# Sheet3.net
KiCad netlist of a schematic drawn in Altium Designer
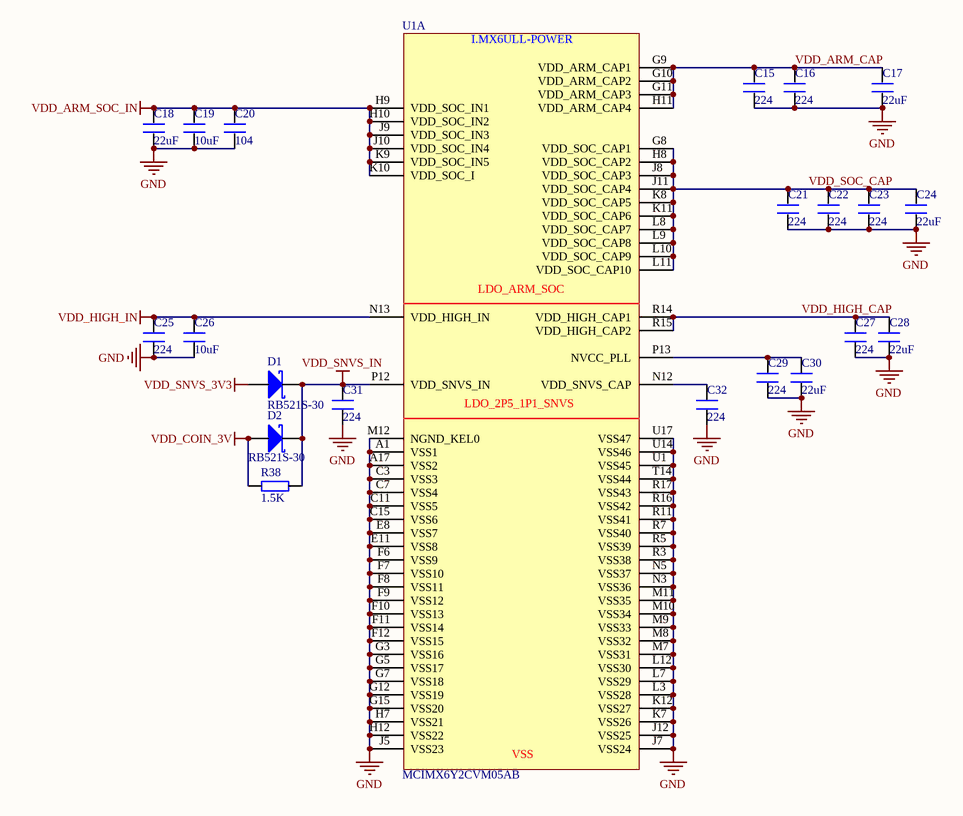
[diagram p0: Sheet3.SchDoc]

(export (version "E")
  (design (tool "Eeschema 10.0.6"))
  (components
    (comp (ref "C15")
      (value "224")
      (footprint "C 0402")
      (libsource (lib "IMX6ULL_CORE(核心板)_V1.4") (part "C"))
    )
    (comp (ref "C16")
      (value "224")
      (footprint "C 0402")
      (libsource (lib "IMX6ULL_CORE(核心板)_V1.4") (part "C"))
    )
    (comp (ref "C17")
      (value "22uF")
      (footprint "C 0402")
      (libsource (lib "IMX6ULL_CORE(核心板)_V1.4") (part "C"))
    )
    (comp (ref "C18")
      (value "22uF")
      (footprint "C 0402")
      (libsource (lib "IMX6ULL_CORE(核心板)_V1.4") (part "C"))
    )
    (comp (ref "C19")
      (value "10uF")
      (footprint "C 0402")
      (libsource (lib "IMX6ULL_CORE(核心板)_V1.4") (part "C"))
    )
    (comp (ref "C20")
      (value "104")
      (footprint "C 0402")
      (libsource (lib "IMX6ULL_CORE(核心板)_V1.4") (part "C"))
    )
    (comp (ref "C21")
      (value "224")
      (footprint "C 0402")
      (libsource (lib "IMX6ULL_CORE(核心板)_V1.4") (part "C"))
    )
    (comp (ref "C22")
      (value "224")
      (footprint "C 0402")
      (libsource (lib "IMX6ULL_CORE(核心板)_V1.4") (part "C"))
    )
    (comp (ref "C23")
      (value "224")
      (footprint "C 0402")
      (libsource (lib "IMX6ULL_CORE(核心板)_V1.4") (part "C"))
    )
    (comp (ref "C24")
      (value "22uF")
      (footprint "C 0402")
      (libsource (lib "IMX6ULL_CORE(核心板)_V1.4") (part "C"))
    )
    (comp (ref "C25")
      (value "224")
      (footprint "C 0402")
      (libsource (lib "IMX6ULL_CORE(核心板)_V1.4") (part "C"))
    )
    (comp (ref "C26")
      (value "10uF")
      (footprint "C 0402")
      (libsource (lib "IMX6ULL_CORE(核心板)_V1.4") (part "C"))
    )
    (comp (ref "C27")
      (value "224")
      (footprint "C 0402")
      (libsource (lib "IMX6ULL_CORE(核心板)_V1.4") (part "C"))
    )
    (comp (ref "C28")
      (value "22uF")
      (footprint "C 0402")
      (libsource (lib "IMX6ULL_CORE(核心板)_V1.4") (part "C"))
    )
    (comp (ref "C29")
      (value "224")
      (footprint "C 0402")
      (libsource (lib "IMX6ULL_CORE(核心板)_V1.4") (part "C"))
    )
    (comp (ref "C30")
      (value "22uF")
      (footprint "C 0402")
      (libsource (lib "IMX6ULL_CORE(核心板)_V1.4") (part "C"))
    )
    (comp (ref "C31")
      (value "224")
      (footprint "C 0402")
      (libsource (lib "IMX6ULL_CORE(核心板)_V1.4") (part "C"))
    )
    (comp (ref "C32")
      (value "224")
      (footprint "C 0402")
      (libsource (lib "IMX6ULL_CORE(核心板)_V1.4") (part "C"))
    )
    (comp (ref "D1")
      (value "RB521S-30")
      (footprint "SOD-523")
      (libsource (lib "IMX6ULL_CORE(核心板)_V1.4") (part "RB521S-30"))
    )
    (comp (ref "D2")
      (value "RB521S-30")
      (footprint "SOD-523")
      (libsource (lib "IMX6ULL_CORE(核心板)_V1.4") (part "RB521S-30"))
    )
    (comp (ref "R38")
      (value "1.5K")
      (footprint "R 0402")
      (libsource (lib "IMX6ULL_CORE(核心板)_V1.4") (part "R"))
    )
    (comp (ref "U1")
      (value "MCIMX6Y2CVM05AB")
      (footprint "BGA289C80P17X17_1400X1400X132")
      (libsource (lib "IMX6ULL_CORE(核心板)_V1.4") (part "MCIMX6Y2CVM05AB"))
    )
  )
  (nets
    (net (code "1") (name "/VDD_ARM_CAP") (class "Default")
      (node (ref "C15") (pin "2") (pintype "passive"))
      (node (ref "C16") (pin "2") (pintype "passive"))
      (node (ref "C17") (pin "2") (pintype "passive"))
      (node (ref "U1") (pin "G10") (pinfunction "VDD_ARM_CAP2_G10") (pintype "passive"))
      (node (ref "U1") (pin "G11") (pinfunction "VDD_ARM_CAP3_G11") (pintype "passive"))
      (node (ref "U1") (pin "G9") (pinfunction "VDD_ARM_CAP1_G9") (pintype "passive"))
      (node (ref "U1") (pin "H11") (pinfunction "VDD_ARM_CAP4_H11") (pintype "passive"))
    )
    (net (code "2") (name "/VDD_HIGH_CAP") (class "Default")
      (node (ref "C27") (pin "2") (pintype "passive"))
      (node (ref "C28") (pin "2") (pintype "passive"))
      (node (ref "U1") (pin "R14") (pinfunction "VDD_HIGH_CAP1_R14") (pintype "passive"))
      (node (ref "U1") (pin "R15") (pinfunction "VDD_HIGH_CAP2_R15") (pintype "passive"))
    )
    (net (code "3") (name "/VDD_SOC_CAP") (class "Default")
      (node (ref "C21") (pin "2") (pintype "passive"))
      (node (ref "C22") (pin "2") (pintype "passive"))
      (node (ref "C23") (pin "2") (pintype "passive"))
      (node (ref "C24") (pin "2") (pintype "passive"))
      (node (ref "U1") (pin "G8") (pinfunction "VDD_SOC_CAP1_G8") (pintype "passive"))
      (node (ref "U1") (pin "H8") (pinfunction "VDD_SOC_CAP2_H8") (pintype "passive"))
      (node (ref "U1") (pin "J11") (pinfunction "VDD_SOC_CAP4_J11") (pintype "passive"))
      (node (ref "U1") (pin "J8") (pinfunction "VDD_SOC_CAP3_J8") (pintype "passive"))
      (node (ref "U1") (pin "K11") (pinfunction "VDD_SOC_CAP6_K11") (pintype "passive"))
      (node (ref "U1") (pin "K8") (pinfunction "VDD_SOC_CAP5_K8") (pintype "passive"))
      (node (ref "U1") (pin "L10") (pinfunction "VDD_SOC_CAP9_L10") (pintype "passive"))
      (node (ref "U1") (pin "L11") (pinfunction "VDD_SOC_CAP10_L11") (pintype "passive"))
      (node (ref "U1") (pin "L8") (pinfunction "VDD_SOC_CAP7_L8") (pintype "passive"))
      (node (ref "U1") (pin "L9") (pinfunction "VDD_SOC_CAP8_L9") (pintype "passive"))
    )
    (net (code "4") (name "GND") (class "Default")
      (node (ref "C15") (pin "1") (pintype "passive"))
      (node (ref "C16") (pin "1") (pintype "passive"))
      (node (ref "C17") (pin "1") (pintype "passive"))
      (node (ref "C18") (pin "1") (pintype "passive"))
      (node (ref "C19") (pin "1") (pintype "passive"))
      (node (ref "C20") (pin "1") (pintype "passive"))
      (node (ref "C21") (pin "1") (pintype "passive"))
      (node (ref "C22") (pin "1") (pintype "passive"))
      (node (ref "C23") (pin "1") (pintype "passive"))
      (node (ref "C24") (pin "1") (pintype "passive"))
      (node (ref "C25") (pin "1") (pintype "passive"))
      (node (ref "C26") (pin "1") (pintype "passive"))
      (node (ref "C27") (pin "1") (pintype "passive"))
      (node (ref "C28") (pin "1") (pintype "passive"))
      (node (ref "C29") (pin "1") (pintype "passive"))
      (node (ref "C30") (pin "1") (pintype "passive"))
      (node (ref "C31") (pin "1") (pintype "passive"))
      (node (ref "C32") (pin "1") (pintype "passive"))
      (node (ref "U1") (pin "A1") (pinfunction "VSS1_A1") (pintype "passive"))
      (node (ref "U1") (pin "A17") (pinfunction "VSS2_A17") (pintype "passive"))
      (node (ref "U1") (pin "C11") (pinfunction "VSS5_C11") (pintype "passive"))
      (node (ref "U1") (pin "C15") (pinfunction "VSS6_C15") (pintype "passive"))
      (node (ref "U1") (pin "C3") (pinfunction "VSS3_C3") (pintype "passive"))
      (node (ref "U1") (pin "C7") (pinfunction "VSS4_C7") (pintype "passive"))
      (node (ref "U1") (pin "E11") (pinfunction "VSS8_E11") (pintype "passive"))
      (node (ref "U1") (pin "E8") (pinfunction "VSS7_E8") (pintype "passive"))
      (node (ref "U1") (pin "F10") (pinfunction "VSS13_F10") (pintype "passive"))
      (node (ref "U1") (pin "F11") (pinfunction "VSS14_F11") (pintype "passive"))
      (node (ref "U1") (pin "F12") (pinfunction "VSS15_F12") (pintype "passive"))
      (node (ref "U1") (pin "F6") (pinfunction "VSS9_F6") (pintype "passive"))
      (node (ref "U1") (pin "F7") (pinfunction "VSS10_F7") (pintype "passive"))
      (node (ref "U1") (pin "F8") (pinfunction "VSS11_F8") (pintype "passive"))
      (node (ref "U1") (pin "F9") (pinfunction "VSS12_F9") (pintype "passive"))
      (node (ref "U1") (pin "G12") (pinfunction "VSS19_G12") (pintype "passive"))
      (node (ref "U1") (pin "G15") (pinfunction "VSS20_G15") (pintype "passive"))
      (node (ref "U1") (pin "G3") (pinfunction "VSS16_G3") (pintype "passive"))
      (node (ref "U1") (pin "G5") (pinfunction "VSS17_G5") (pintype "passive"))
      (node (ref "U1") (pin "G7") (pinfunction "VSS18_G7") (pintype "passive"))
      (node (ref "U1") (pin "H12") (pinfunction "VSS22_H12") (pintype "passive"))
      (node (ref "U1") (pin "H7") (pinfunction "VSS21_H7") (pintype "passive"))
      (node (ref "U1") (pin "J12") (pinfunction "VSS25_J12") (pintype "passive"))
      (node (ref "U1") (pin "J5") (pinfunction "VSS23_J5") (pintype "passive"))
      (node (ref "U1") (pin "J7") (pinfunction "VSS24_J7") (pintype "passive"))
      (node (ref "U1") (pin "K12") (pinfunction "VSS27_K12") (pintype "passive"))
      (node (ref "U1") (pin "K7") (pinfunction "VSS26_K7") (pintype "passive"))
      (node (ref "U1") (pin "L12") (pinfunction "VSS30_L12") (pintype "passive"))
      (node (ref "U1") (pin "L3") (pinfunction "VSS28_L3") (pintype "passive"))
      (node (ref "U1") (pin "L7") (pinfunction "VSS29_L7") (pintype "passive"))
      (node (ref "U1") (pin "M10") (pinfunction "VSS34_M10") (pintype "passive"))
      (node (ref "U1") (pin "M11") (pinfunction "VSS35_M11") (pintype "passive"))
      (node (ref "U1") (pin "M12") (pinfunction "NGND_KEL0_M12") (pintype "passive"))
      (node (ref "U1") (pin "M7") (pinfunction "VSS31_M7") (pintype "passive"))
      (node (ref "U1") (pin "M8") (pinfunction "VSS32_M8") (pintype "passive"))
      (node (ref "U1") (pin "M9") (pinfunction "VSS33_M9") (pintype "passive"))
      (node (ref "U1") (pin "N3") (pinfunction "VSS36_N3") (pintype "passive"))
      (node (ref "U1") (pin "N5") (pinfunction "VSS37_N5") (pintype "passive"))
      (node (ref "U1") (pin "R11") (pinfunction "VSS41_R11") (pintype "passive"))
      (node (ref "U1") (pin "R16") (pinfunction "VSS42_R16") (pintype "passive"))
      (node (ref "U1") (pin "R17") (pinfunction "VSS43_R17") (pintype "passive"))
      (node (ref "U1") (pin "R3") (pinfunction "VSS38_R3") (pintype "passive"))
      (node (ref "U1") (pin "R5") (pinfunction "VSS39_R5") (pintype "passive"))
      (node (ref "U1") (pin "R7") (pinfunction "VSS40_R7") (pintype "passive"))
      (node (ref "U1") (pin "T14") (pinfunction "VSS44_T14") (pintype "passive"))
      (node (ref "U1") (pin "U1") (pinfunction "VSS45_U1") (pintype "passive"))
      (node (ref "U1") (pin "U14") (pinfunction "VSS46_U14") (pintype "passive"))
      (node (ref "U1") (pin "U17") (pinfunction "VSS47_U17") (pintype "passive"))
    )
    (net (code "5") (name "Net-(U1A-NVCC_PLL)") (class "Default")
      (node (ref "C29") (pin "2") (pintype "passive"))
      (node (ref "C30") (pin "2") (pintype "passive"))
      (node (ref "U1") (pin "P13") (pinfunction "NVCC_PLL_P13") (pintype "passive"))
    )
    (net (code "6") (name "Net-(U1A-VDD_SNVS_CAP)") (class "Default")
      (node (ref "C32") (pin "2") (pintype "passive"))
      (node (ref "U1") (pin "N12") (pinfunction "VDD_SNVS_CAP_N12") (pintype "passive"))
    )
    (net (code "7") (name "VDD_ARM_SOC_IN") (class "Default")
      (node (ref "C18") (pin "2") (pintype "passive"))
      (node (ref "C19") (pin "2") (pintype "passive"))
      (node (ref "C20") (pin "2") (pintype "passive"))
      (node (ref "U1") (pin "H10") (pinfunction "VDD_SOC_IN2_H10") (pintype "passive"))
      (node (ref "U1") (pin "H9") (pinfunction "VDD_SOC_IN1_H9") (pintype "passive"))
      (node (ref "U1") (pin "J10") (pinfunction "VDD_SOC_IN4_J10") (pintype "passive"))
      (node (ref "U1") (pin "J9") (pinfunction "VDD_SOC_IN3_J9") (pintype "passive"))
      (node (ref "U1") (pin "K10") (pinfunction "VDD_SOC_I_K10") (pintype "passive"))
      (node (ref "U1") (pin "K9") (pinfunction "VDD_SOC_IN5_K9") (pintype "passive"))
    )
    (net (code "8") (name "VDD_COIN_3V") (class "Default")
      (node (ref "D2") (pin "1") (pinfunction "A_1") (pintype "passive"))
      (node (ref "R38") (pin "1") (pintype "passive"))
    )
    (net (code "9") (name "VDD_HIGH_IN") (class "Default")
      (node (ref "C25") (pin "2") (pintype "passive"))
      (node (ref "C26") (pin "2") (pintype "passive"))
      (node (ref "U1") (pin "N13") (pinfunction "VDD_HIGH_IN_N13") (pintype "passive"))
    )
    (net (code "10") (name "VDD_SNVS_3V3") (class "Default")
      (node (ref "D1") (pin "1") (pinfunction "A_1") (pintype "passive"))
    )
    (net (code "11") (name "VDD_SNVS_IN") (class "Default")
      (node (ref "C31") (pin "2") (pintype "passive"))
      (node (ref "D1") (pin "2") (pinfunction "C_2") (pintype "passive"))
      (node (ref "D2") (pin "2") (pinfunction "C_2") (pintype "passive"))
      (node (ref "R38") (pin "2") (pintype "passive"))
      (node (ref "U1") (pin "P12") (pinfunction "VDD_SNVS_IN_P12") (pintype "passive"))
    )
  )
)
